# Status_LEDs.net
KiCad netlist of a schematic drawn in Altium Designer
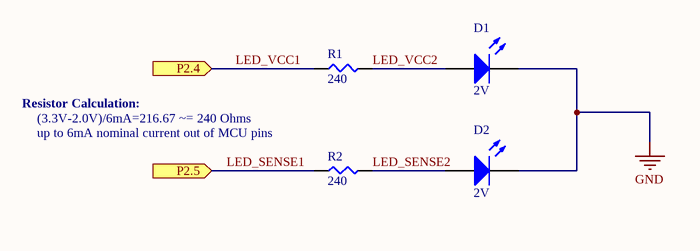
[diagram p0: Status LEDs.SchDoc]

(export (version "E")
  (design (tool "Eeschema 10.0.6"))
  (components
    (comp (ref "D1")
      (value "2V")
      (footprint "0805_A")
      (description "SMD mono-color Chip LED, WL-SMCW, Bright Green")
      (fields (field (name "PARTNUMBER") "150080VS75000") (field (name "MANUFACTURER") "Wuerth Elektronik"))
      (libsource (lib "Altium Content Vault") (part "WE-LED_K1A2-2"))
    )
    (comp (ref "D2")
      (value "2V")
      (footprint "0805_A")
      (description "SMD mono-color Chip LED, WL-SMCW, Bright Green")
      (fields (field (name "PARTNUMBER") "150080VS75000") (field (name "MANUFACTURER") "Wuerth Elektronik"))
      (libsource (lib "Altium Content Vault") (part "WE-LED_K1A2-2"))
    )
    (comp (ref "R1")
      (value "240")
      (footprint "SMD-0805-RES")
      (description "RES SMD 240 OHM 1% 1/8W 0805")
      (fields (field (name "PART NUMBER") "ERJ-6ENF2400V") (field (name "DIGI-KEY PART NUMBER") "P240CCT-ND"))
      (libsource (lib "Panasonic_resistor_0805") (part "ERJ-6ENF2400V"))
    )
    (comp (ref "R2")
      (value "240")
      (footprint "SMD-0805-RES")
      (description "RES SMD 240 OHM 1% 1/8W 0805")
      (fields (field (name "PART NUMBER") "ERJ-6ENF2400V") (field (name "DIGI-KEY PART NUMBER") "P240CCT-ND"))
      (libsource (lib "Panasonic_resistor_0805") (part "ERJ-6ENF2400V"))
    )
  )
  (nets
    (net (code "1") (name "/LED_SENSE1") (class "Default")
      (node (ref "R2") (pin "1") (pinfunction "1_1") (pintype "passive"))
    )
    (net (code "2") (name "/LED_SENSE2") (class "Default")
      (node (ref "D2") (pin "2") (pinfunction "A_2") (pintype "passive"))
      (node (ref "R2") (pin "2") (pinfunction "2_2") (pintype "passive"))
    )
    (net (code "3") (name "/LED_VCC1") (class "Default")
      (node (ref "R1") (pin "1") (pinfunction "1_1") (pintype "passive"))
    )
    (net (code "4") (name "/LED_VCC2") (class "Default")
      (node (ref "D1") (pin "2") (pinfunction "A_2") (pintype "passive"))
      (node (ref "R1") (pin "2") (pinfunction "2_2") (pintype "passive"))
    )
    (net (code "5") (name "GND") (class "Default")
      (node (ref "D1") (pin "1") (pinfunction "K_1") (pintype "passive"))
      (node (ref "D2") (pin "1") (pinfunction "K_1") (pintype "passive"))
    )
  )
)
